# vinciDuino.net
KiCad netlist of a schematic drawn in EAGLE
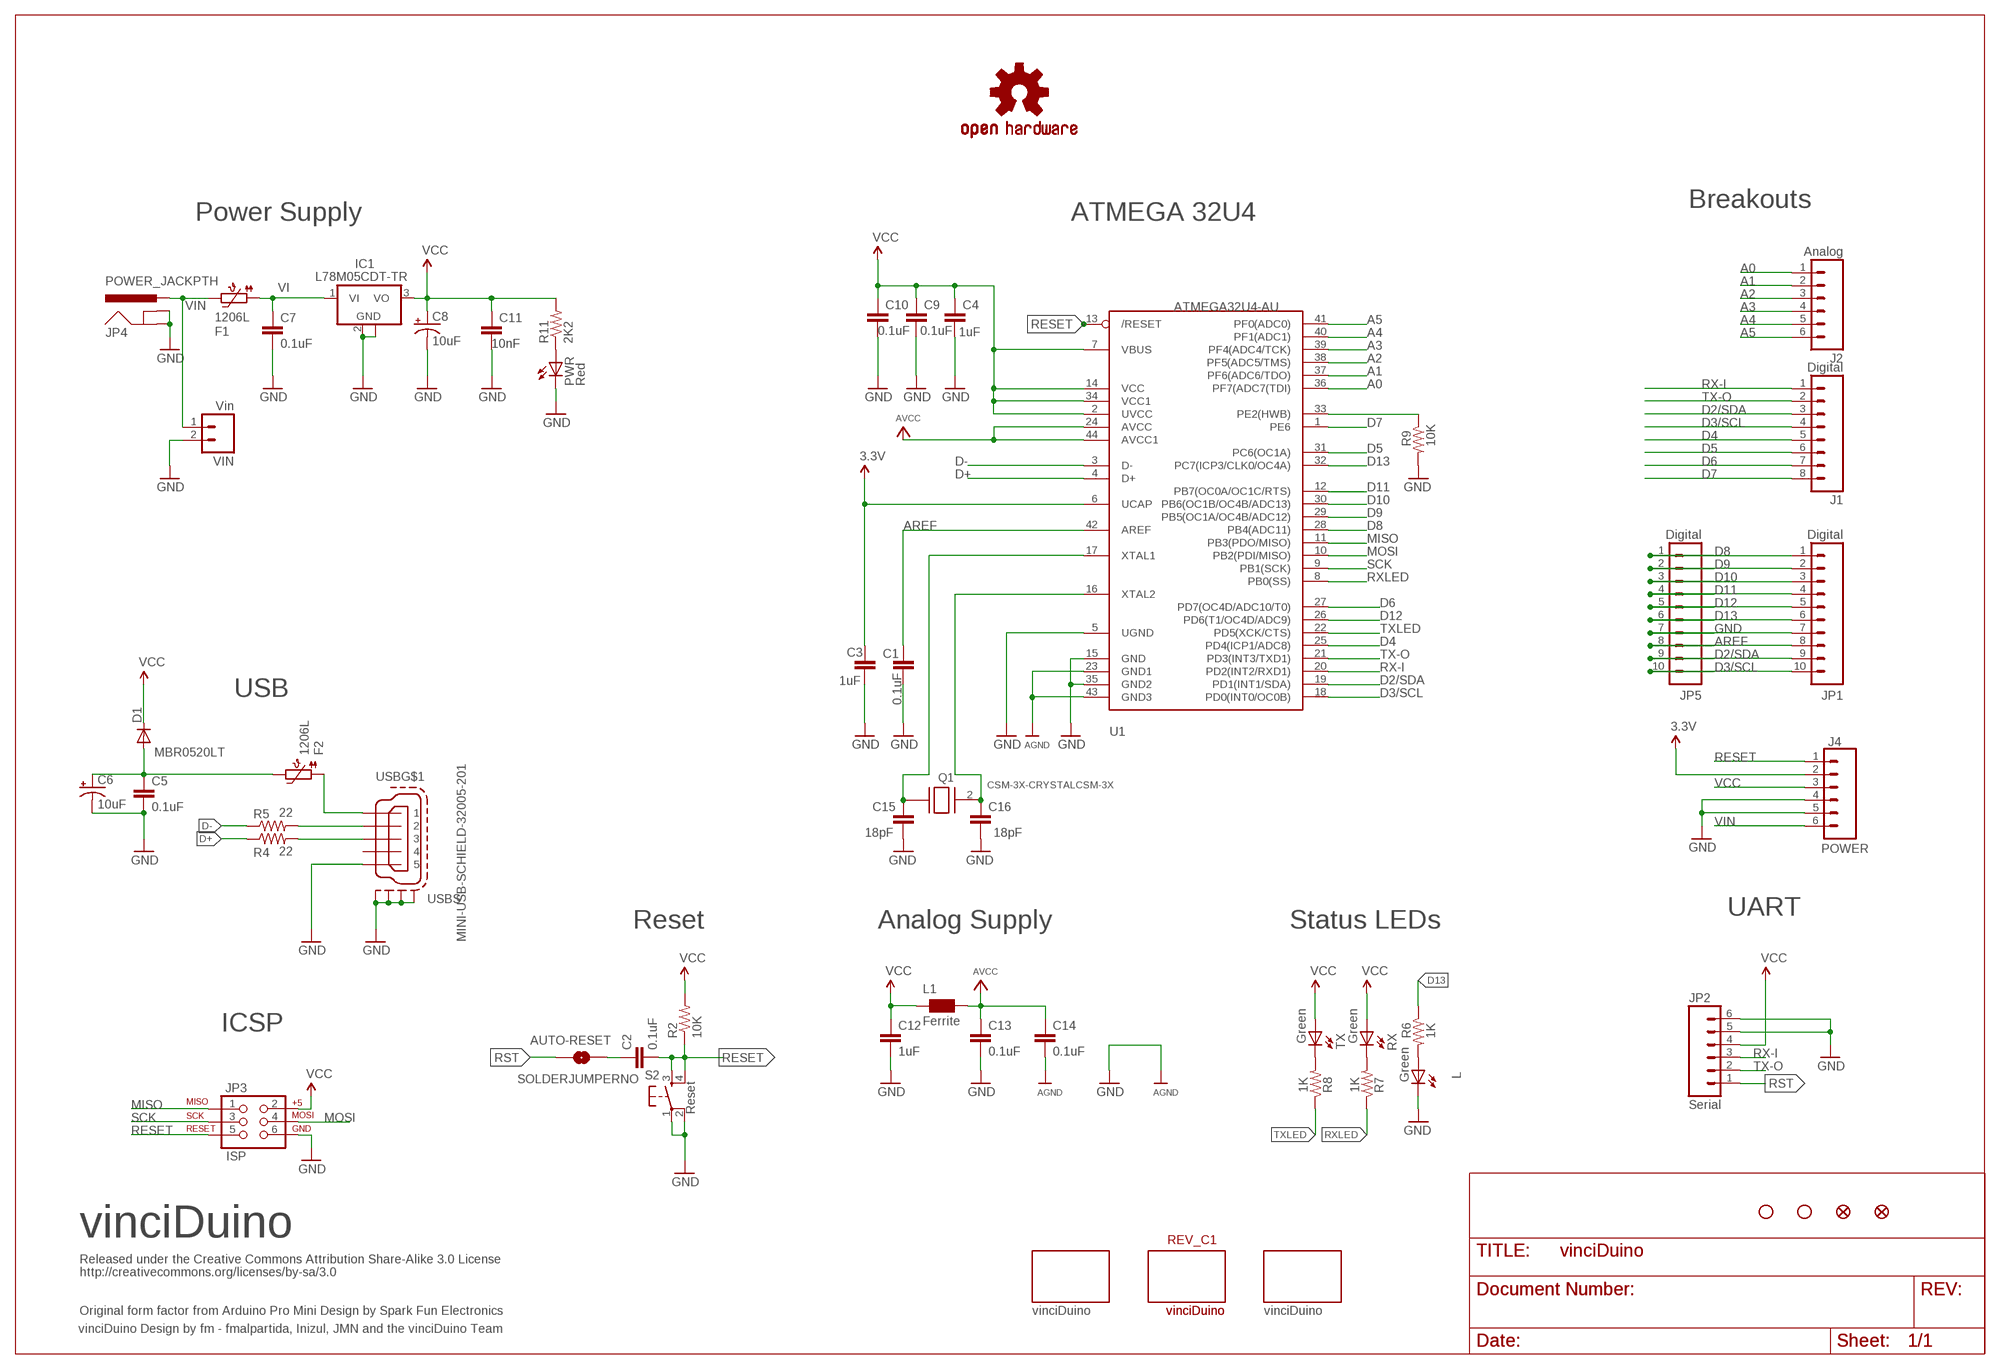
[diagram p0: schematic, sheet 1]

(export (version "E")
  (design (tool "Eeschema 10.0.6"))
  (components
    (comp (ref "AUTO-RESET")
      (value "SOLDERJUMPERNO")
      (footprint "eagle-import:SJ_2S-NO")
      (libsource (lib "eagle-import") (part "SOLDERJUMPERNO"))
    )
    (comp (ref "C1")
      (value "0.1uF")
      (footprint "eagle-import:1206")
      (libsource (lib "eagle-import") (part "CAP1206"))
    )
    (comp (ref "C2")
      (value "0.1uF")
      (footprint "eagle-import:1206")
      (libsource (lib "eagle-import") (part "CAP1206"))
    )
    (comp (ref "C3")
      (value "1uF")
      (footprint "eagle-import:1206")
      (libsource (lib "eagle-import") (part "CAP1206"))
    )
    (comp (ref "C4")
      (value "1uF")
      (footprint "eagle-import:1206")
      (libsource (lib "eagle-import") (part "CAP1206"))
    )
    (comp (ref "C5")
      (value "0.1uF")
      (footprint "eagle-import:1206")
      (libsource (lib "eagle-import") (part "CAP1206"))
    )
    (comp (ref "C6")
      (value "10uF")
      (footprint "eagle-import:EIA3216")
      (libsource (lib "eagle-import") (part "CAP_POL1206"))
    )
    (comp (ref "C7")
      (value "0.1uF")
      (footprint "eagle-import:1206")
      (libsource (lib "eagle-import") (part "CAP1206"))
    )
    (comp (ref "C8")
      (value "10uF")
      (footprint "eagle-import:EIA3216")
      (libsource (lib "eagle-import") (part "CAP_POL1206"))
    )
    (comp (ref "C9")
      (value "0.1uF")
      (footprint "eagle-import:1206")
      (libsource (lib "eagle-import") (part "CAP1206"))
    )
    (comp (ref "C10")
      (value "0.1uF")
      (footprint "eagle-import:1206")
      (libsource (lib "eagle-import") (part "CAP1206"))
    )
    (comp (ref "C11")
      (value "10nF")
      (footprint "eagle-import:1206")
      (libsource (lib "eagle-import") (part "CAP1206"))
    )
    (comp (ref "C12")
      (value "1uF")
      (footprint "eagle-import:1206")
      (libsource (lib "eagle-import") (part "CAP1206"))
    )
    (comp (ref "C13")
      (value "0.1uF")
      (footprint "eagle-import:1206")
      (libsource (lib "eagle-import") (part "CAP1206"))
    )
    (comp (ref "C14")
      (value "0.1uF")
      (footprint "eagle-import:1206")
      (libsource (lib "eagle-import") (part "CAP1206"))
    )
    (comp (ref "C15")
      (value "18pF")
      (footprint "eagle-import:1206")
      (libsource (lib "eagle-import") (part "CAP1206"))
    )
    (comp (ref "C16")
      (value "18pF")
      (footprint "eagle-import:1206")
      (libsource (lib "eagle-import") (part "CAP1206"))
    )
    (comp (ref "D1")
      (value "MBR0520LT")
      (footprint "eagle-import:SOD123")
      (libsource (lib "eagle-import") (part "MBR0520LT"))
    )
    (comp (ref "F1")
      (value "1206L")
      (footprint "eagle-import:1206_PTC")
      (libsource (lib "eagle-import") (part "PTC1206_L"))
    )
    (comp (ref "F2")
      (value "1206L")
      (footprint "eagle-import:1206_PTC")
      (libsource (lib "eagle-import") (part "PTC1206_L"))
    )
    (comp (ref "IC1")
      (value "L78M05CDT-TR")
      (footprint "eagle-import:SOT-223-DPAK")
      (libsource (lib "eagle-import") (part "78XX"))
    )
    (comp (ref "J1")
      (value "Digital")
      (footprint "eagle-import:1X08")
      (libsource (lib "eagle-import") (part "M081X08"))
    )
    (comp (ref "J2")
      (value "Analog")
      (footprint "eagle-import:1X06")
      (libsource (lib "eagle-import") (part "M06SIP"))
    )
    (comp (ref "J4")
      (value "POWER")
      (footprint "eagle-import:1X06")
      (libsource (lib "eagle-import") (part "M06SIP"))
    )
    (comp (ref "JP1")
      (value "Digital")
      (footprint "eagle-import:1X10")
      (libsource (lib "eagle-import") (part "M10{dblquote}"))
    )
    (comp (ref "JP2")
      (value "Serial")
      (footprint "eagle-import:1X06")
      (libsource (lib "eagle-import") (part "M06SIP"))
    )
    (comp (ref "JP3")
      (value "ISP")
      (footprint "eagle-import:2X3")
      (libsource (lib "eagle-import") (part "AVR_SPI_PRG_6PTH"))
    )
    (comp (ref "JP4")
      (value "POWER_JACKPTH")
      (footprint "eagle-import:POWER_JACK_PTH")
      (libsource (lib "eagle-import") (part "POWER_JACKPTH"))
    )
    (comp (ref "JP5")
      (value "Digital")
      (footprint "eagle-import:1X10")
      (libsource (lib "eagle-import") (part "M10{dblquote}"))
    )
    (comp (ref "L")
      (value "Green")
      (footprint "eagle-import:LED-1206")
      (libsource (lib "eagle-import") (part "LED1206"))
    )
    (comp (ref "L1")
      (value "Ferrite")
      (footprint "eagle-import:1206W")
      (libsource (lib "eagle-import") (part "WE-CBF_1206W"))
    )
    (comp (ref "PWR")
      (value "Red")
      (footprint "eagle-import:LED-1206")
      (libsource (lib "eagle-import") (part "LED1206"))
    )
    (comp (ref "Q1")
      (value "CSM-3X-CRYSTALCSM-3X")
      (footprint "eagle-import:CSM-3X")
      (libsource (lib "eagle-import") (part "CSM-3X-CRYSTALCSM-3X"))
    )
    (comp (ref "R2")
      (value "10K")
      (footprint "eagle-import:R1206")
      (libsource (lib "eagle-import") (part "R-US_R1206"))
    )
    (comp (ref "R4")
      (value "22")
      (footprint "eagle-import:R1206")
      (libsource (lib "eagle-import") (part "R-US_R1206"))
    )
    (comp (ref "R5")
      (value "22")
      (footprint "eagle-import:R1206")
      (libsource (lib "eagle-import") (part "R-US_R1206"))
    )
    (comp (ref "R6")
      (value "1K")
      (footprint "eagle-import:R1206")
      (libsource (lib "eagle-import") (part "R-US_R1206"))
    )
    (comp (ref "R7")
      (value "1K")
      (footprint "eagle-import:R1206")
      (libsource (lib "eagle-import") (part "R-US_R1206"))
    )
    (comp (ref "R8")
      (value "1K")
      (footprint "eagle-import:R1206")
      (libsource (lib "eagle-import") (part "R-US_R1206"))
    )
    (comp (ref "R9")
      (value "10K")
      (footprint "eagle-import:R1206")
      (libsource (lib "eagle-import") (part "R-US_R1206"))
    )
    (comp (ref "R11")
      (value "2K2")
      (footprint "eagle-import:R1206")
      (libsource (lib "eagle-import") (part "R-US_R1206"))
    )
    (comp (ref "REV_C1")
      (value "vinciDuino")
      (footprint "eagle-import:ARDUINO_FORUM")
      (libsource (lib "eagle-import") (part "BOARD_INFO_"))
    )
    (comp (ref "RX")
      (value "Green")
      (footprint "eagle-import:LED-1206")
      (libsource (lib "eagle-import") (part "LED1206"))
    )
    (comp (ref "S2")
      (value "Reset")
      (footprint "eagle-import:TACTILE_SWITCH_SMD")
      (libsource (lib "eagle-import") (part "TAC_SWITCHSMD"))
    )
    (comp (ref "TX")
      (value "Green")
      (footprint "eagle-import:LED-1206")
      (libsource (lib "eagle-import") (part "LED1206"))
    )
    (comp (ref "U$1")
      (value "VINCIDUINO_")
      (footprint "eagle-import:VINCIDUINO")
      (libsource (lib "eagle-import") (part "VINCIDUINO_25"))
    )
    (comp (ref "U$2")
      (value "FIDUCIAL1X2")
      (footprint "eagle-import:FIDUCIAL-1X2")
      (libsource (lib "eagle-import") (part "FIDUCIAL1X2"))
    )
    (comp (ref "U$3")
      (value "VINCIDUINO_15")
      (footprint "eagle-import:VINCIDUINO_VSMAL")
      (libsource (lib "eagle-import") (part "VINCIDUINO_15"))
    )
    (comp (ref "U$4")
      (value "FIDUCIAL1X2")
      (footprint "eagle-import:FIDUCIAL-1X2")
      (libsource (lib "eagle-import") (part "FIDUCIAL1X2"))
    )
    (comp (ref "U$9")
      (value "STAND-OFF")
      (footprint "eagle-import:STAND-OFF")
      (libsource (lib "eagle-import") (part "STAND-OFF"))
    )
    (comp (ref "U$10")
      (value "STAND-OFF")
      (footprint "eagle-import:STAND-OFF")
      (libsource (lib "eagle-import") (part "STAND-OFF"))
    )
    (comp (ref "U$14")
      (value "OSHW-LOGOS")
      (footprint "eagle-import:OSHW-LOGO-S")
      (libsource (lib "eagle-import") (part "OSHW-LOGOS"))
    )
    (comp (ref "U1")
      (value "ATMEGA32U4-AU")
      (footprint "eagle-import:TQFP44")
      (libsource (lib "eagle-import") (part "ATMEGA32U4-AU"))
    )
    (comp (ref "USB")
      (value "MINI-USB-SCHIELD-32005-201")
      (footprint "eagle-import:32005-201")
      (libsource (lib "eagle-import") (part "MINI-USB-SCHIELD-32005-201"))
    )
    (comp (ref "VIN")
      (value "Vin")
      (footprint "eagle-import:1X02_NO_SILK")
      (libsource (lib "eagle-import") (part "M021X02_NO_SILK"))
    )
  )
  (nets
    (net (code "1") (name "/A0") (class "Default")
      (node (ref "J2") (pin "1") (pinfunction "1_1") (pintype "passive"))
      (node (ref "U1") (pin "36") (pinfunction "PF7(ADC7(TDI)_36") (pintype "bidirectional"))
    )
    (net (code "2") (name "/A1") (class "Default")
      (node (ref "J2") (pin "2") (pinfunction "2_2") (pintype "passive"))
      (node (ref "U1") (pin "37") (pinfunction "PF6(ADC6/TDO)_37") (pintype "bidirectional"))
    )
    (net (code "3") (name "/A2") (class "Default")
      (node (ref "J2") (pin "3") (pinfunction "3_3") (pintype "passive"))
      (node (ref "U1") (pin "38") (pinfunction "PF5(ADC5/TMS)_38") (pintype "bidirectional"))
    )
    (net (code "4") (name "/A3") (class "Default")
      (node (ref "J2") (pin "4") (pinfunction "4_4") (pintype "passive"))
      (node (ref "U1") (pin "39") (pinfunction "PF4(ADC4/TCK)_39") (pintype "bidirectional"))
    )
    (net (code "5") (name "/A4") (class "Default")
      (node (ref "J2") (pin "5") (pinfunction "5_5") (pintype "passive"))
      (node (ref "U1") (pin "40") (pinfunction "PF1(ADC1)_40") (pintype "bidirectional"))
    )
    (net (code "6") (name "/A5") (class "Default")
      (node (ref "J2") (pin "6") (pinfunction "6_6") (pintype "passive"))
      (node (ref "U1") (pin "41") (pinfunction "PF0(ADC0)_41") (pintype "bidirectional"))
    )
    (net (code "7") (name "/AREF") (class "Default")
      (node (ref "C1") (pin "2") (pinfunction "2_2") (pintype "passive"))
      (node (ref "JP1") (pin "8") (pinfunction "8_8") (pintype "passive"))
      (node (ref "JP5") (pin "8") (pinfunction "8_8") (pintype "passive"))
      (node (ref "U1") (pin "42") (pinfunction "AREF_42") (pintype "bidirectional"))
    )
    (net (code "8") (name "/D2{slash}SDA") (class "Default")
      (node (ref "J1") (pin "3") (pinfunction "3_3") (pintype "passive"))
      (node (ref "JP1") (pin "9") (pinfunction "9_9") (pintype "passive"))
      (node (ref "JP5") (pin "9") (pinfunction "9_9") (pintype "passive"))
      (node (ref "U1") (pin "19") (pinfunction "PD1(INT1/SDA)_19") (pintype "bidirectional"))
    )
    (net (code "9") (name "/D3{slash}SCL") (class "Default")
      (node (ref "J1") (pin "4") (pinfunction "4_4") (pintype "passive"))
      (node (ref "JP1") (pin "10") (pinfunction "10_10") (pintype "passive"))
      (node (ref "JP5") (pin "10") (pinfunction "10_10") (pintype "passive"))
      (node (ref "U1") (pin "18") (pinfunction "PD0(INT0/OC0B)_18") (pintype "bidirectional"))
    )
    (net (code "10") (name "/D4") (class "Default")
      (node (ref "J1") (pin "5") (pinfunction "5_5") (pintype "passive"))
      (node (ref "U1") (pin "25") (pinfunction "PD4(ICP1/ADC8)_25") (pintype "bidirectional"))
    )
    (net (code "11") (name "/D5") (class "Default")
      (node (ref "J1") (pin "6") (pinfunction "6_6") (pintype "passive"))
      (node (ref "U1") (pin "31") (pinfunction "PC6(OC1A)_31") (pintype "bidirectional"))
    )
    (net (code "12") (name "/D6") (class "Default")
      (node (ref "J1") (pin "7") (pinfunction "7_7") (pintype "passive"))
      (node (ref "U1") (pin "27") (pinfunction "PD7(OC4D/ADC10/T0)_27") (pintype "bidirectional"))
    )
    (net (code "13") (name "/D7") (class "Default")
      (node (ref "J1") (pin "8") (pinfunction "8_8") (pintype "passive"))
      (node (ref "U1") (pin "1") (pinfunction "PE6_1") (pintype "bidirectional"))
    )
    (net (code "14") (name "/D8") (class "Default")
      (node (ref "JP1") (pin "1") (pinfunction "1_1") (pintype "passive"))
      (node (ref "JP5") (pin "1") (pinfunction "1_1") (pintype "passive"))
      (node (ref "U1") (pin "28") (pinfunction "PB4(ADC11)_28") (pintype "bidirectional"))
    )
    (net (code "15") (name "/D9") (class "Default")
      (node (ref "JP1") (pin "2") (pinfunction "2_2") (pintype "passive"))
      (node (ref "JP5") (pin "2") (pinfunction "2_2") (pintype "passive"))
      (node (ref "U1") (pin "29") (pinfunction "PB5(OC1A/OC4B/ADC12)_29") (pintype "bidirectional"))
    )
    (net (code "16") (name "/D10") (class "Default")
      (node (ref "JP1") (pin "3") (pinfunction "3_3") (pintype "passive"))
      (node (ref "JP5") (pin "3") (pinfunction "3_3") (pintype "passive"))
      (node (ref "U1") (pin "30") (pinfunction "PB6(OC1B/OC4B/ADC13)_30") (pintype "bidirectional"))
    )
    (net (code "17") (name "/D11") (class "Default")
      (node (ref "JP1") (pin "4") (pinfunction "4_4") (pintype "passive"))
      (node (ref "JP5") (pin "4") (pinfunction "4_4") (pintype "passive"))
      (node (ref "U1") (pin "12") (pinfunction "PB7(OC0A/OC1C/RTS)_12") (pintype "bidirectional"))
    )
    (net (code "18") (name "/D12") (class "Default")
      (node (ref "JP1") (pin "5") (pinfunction "5_5") (pintype "passive"))
      (node (ref "JP5") (pin "5") (pinfunction "5_5") (pintype "passive"))
      (node (ref "U1") (pin "26") (pinfunction "PD6(T1/OC4D/ADC9)_26") (pintype "bidirectional"))
    )
    (net (code "19") (name "/MISO") (class "Default")
      (node (ref "JP3") (pin "1") (pinfunction "1_1") (pintype "passive"))
      (node (ref "U1") (pin "11") (pinfunction "PB3(PDO/MISO)_11") (pintype "bidirectional"))
    )
    (net (code "20") (name "/MOSI") (class "Default")
      (node (ref "JP3") (pin "4") (pinfunction "4_4") (pintype "passive"))
      (node (ref "U1") (pin "10") (pinfunction "PB2(PDI/MISO)_10") (pintype "bidirectional"))
    )
    (net (code "21") (name "/RX-I") (class "Default")
      (node (ref "J1") (pin "1") (pinfunction "1_1") (pintype "passive"))
      (node (ref "JP2") (pin "3") (pinfunction "3_3") (pintype "passive"))
      (node (ref "U1") (pin "20") (pinfunction "PD2(INT2/RXD1)_20") (pintype "bidirectional"))
    )
    (net (code "22") (name "/SCK") (class "Default")
      (node (ref "JP3") (pin "3") (pinfunction "3_3") (pintype "passive"))
      (node (ref "U1") (pin "9") (pinfunction "PB1(SCK)_9") (pintype "bidirectional"))
    )
    (net (code "23") (name "/TX-O") (class "Default")
      (node (ref "J1") (pin "2") (pinfunction "2_2") (pintype "passive"))
      (node (ref "JP2") (pin "2") (pinfunction "2_2") (pintype "passive"))
      (node (ref "U1") (pin "21") (pinfunction "PD3(INT3/TXD1)_21") (pintype "bidirectional"))
    )
    (net (code "24") (name "/VI") (class "Default")
      (node (ref "C7") (pin "1") (pinfunction "1_1") (pintype "passive"))
      (node (ref "F1") (pin "1") (pinfunction "1_1") (pintype "passive"))
      (node (ref "IC1") (pin "1") (pinfunction "VI_1") (pintype "input"))
    )
    (net (code "25") (name "/VIN") (class "Default")
      (node (ref "F1") (pin "2") (pinfunction "2_2") (pintype "passive"))
      (node (ref "J4") (pin "6") (pinfunction "6_6") (pintype "passive"))
      (node (ref "JP4") (pin "PWR") (pinfunction "PWR_PWR") (pintype "bidirectional"))
      (node (ref "VIN") (pin "1") (pinfunction "1_1") (pintype "passive"))
    )
    (net (code "26") (name "3.3V") (class "Default")
      (node (ref "C3") (pin "1") (pinfunction "1_1") (pintype "passive"))
      (node (ref "J4") (pin "2") (pinfunction "2_2") (pintype "passive"))
      (node (ref "U1") (pin "6") (pinfunction "UCAP_6") (pintype "bidirectional"))
    )
    (net (code "27") (name "AGND") (class "Default")
      (node (ref "C1") (pin "1") (pinfunction "1_1") (pintype "passive"))
      (node (ref "C10") (pin "2") (pinfunction "2_2") (pintype "passive"))
      (node (ref "C11") (pin "2") (pinfunction "2_2") (pintype "passive"))
      (node (ref "C12") (pin "2") (pinfunction "2_2") (pintype "passive"))
      (node (ref "C13") (pin "2") (pinfunction "2_2") (pintype "passive"))
      (node (ref "C14") (pin "2") (pinfunction "2_2") (pintype "passive"))
      (node (ref "C15") (pin "2") (pinfunction "2_2") (pintype "passive"))
      (node (ref "C16") (pin "2") (pinfunction "2_2") (pintype "passive"))
      (node (ref "C3") (pin "2") (pinfunction "2_2") (pintype "passive"))
      (node (ref "C4") (pin "2") (pinfunction "2_2") (pintype "passive"))
      (node (ref "C5") (pin "2") (pinfunction "2_2") (pintype "passive"))
      (node (ref "C6") (pin "C") (pinfunction "-_C") (pintype "passive"))
      (node (ref "C7") (pin "2") (pinfunction "2_2") (pintype "passive"))
      (node (ref "C8") (pin "C") (pinfunction "-_C") (pintype "passive"))
      (node (ref "C9") (pin "2") (pinfunction "2_2") (pintype "passive"))
      (node (ref "IC1") (pin "2") (pinfunction "GND_2") (pintype "passive"))
      (node (ref "IC1") (pin "4") (pinfunction "GND_4") (pintype "passive"))
      (node (ref "J4") (pin "4") (pinfunction "4_4") (pintype "passive"))
      (node (ref "J4") (pin "5") (pinfunction "5_5") (pintype "passive"))
      (node (ref "JP1") (pin "7") (pinfunction "7_7") (pintype "passive"))
      (node (ref "JP2") (pin "5") (pinfunction "5_5") (pintype "passive"))
      (node (ref "JP2") (pin "6") (pinfunction "6_6") (pintype "passive"))
      (node (ref "JP3") (pin "6") (pinfunction "6_6") (pintype "passive"))
      (node (ref "JP4") (pin "GND") (pinfunction "GND_GND") (pintype "bidirectional"))
      (node (ref "JP4") (pin "GNDBREAK") (pinfunction "GNDBREAK_GNDBREAK") (pintype "bidirectional"))
      (node (ref "JP5") (pin "7") (pinfunction "7_7") (pintype "passive"))
      (node (ref "L") (pin "C") (pinfunction "C_C") (pintype "passive"))
      (node (ref "PWR") (pin "C") (pinfunction "C_C") (pintype "passive"))
      (node (ref "R9") (pin "2") (pinfunction "2_2") (pintype "passive"))
      (node (ref "S2") (pin "1") (pinfunction "1_1") (pintype "passive"))
      (node (ref "S2") (pin "2") (pinfunction "2_2") (pintype "passive"))
      (node (ref "U1") (pin "15") (pinfunction "GND_15") (pintype "bidirectional"))
      (node (ref "U1") (pin "23") (pinfunction "GND1_23") (pintype "bidirectional"))
      (node (ref "U1") (pin "35") (pinfunction "GND2_35") (pintype "bidirectional"))
      (node (ref "U1") (pin "43") (pinfunction "GND3_43") (pintype "bidirectional"))
      (node (ref "U1") (pin "5") (pinfunction "UGND_5") (pintype "bidirectional"))
      (node (ref "USB") (pin "5") (pinfunction "5_5") (pintype "passive"))
      (node (ref "USB") (pin "M1") (pinfunction "S1_M1") (pintype "passive"))
      (node (ref "USB") (pin "M2") (pinfunction "S2_M2") (pintype "passive"))
      (node (ref "USB") (pin "M3") (pinfunction "S3_M3") (pintype "passive"))
      (node (ref "USB") (pin "M4") (pinfunction "S4_M4") (pintype "passive"))
      (node (ref "VIN") (pin "2") (pinfunction "2_2") (pintype "passive"))
    )
    (net (code "28") (name "AVCC") (class "Default")
      (node (ref "C13") (pin "1") (pinfunction "1_1") (pintype "passive"))
      (node (ref "C14") (pin "1") (pinfunction "1_1") (pintype "passive"))
      (node (ref "L1") (pin "2") (pinfunction "2_2") (pintype "passive"))
      (node (ref "U1") (pin "24") (pinfunction "AVCC_24") (pintype "bidirectional"))
      (node (ref "U1") (pin "44") (pinfunction "AVCC1_44") (pintype "bidirectional"))
    )
    (net (code "29") (name "D+") (class "Default")
      (node (ref "R4") (pin "1") (pinfunction "1_1") (pintype "passive"))
      (node (ref "U1") (pin "4") (pinfunction "D+_4") (pintype "bidirectional"))
    )
    (net (code "30") (name "D-") (class "Default")
      (node (ref "R5") (pin "1") (pinfunction "1_1") (pintype "passive"))
      (node (ref "U1") (pin "3") (pinfunction "D-_3") (pintype "bidirectional"))
    )
    (net (code "31") (name "D13") (class "Default")
      (node (ref "JP1") (pin "6") (pinfunction "6_6") (pintype "passive"))
      (node (ref "JP5") (pin "6") (pinfunction "6_6") (pintype "passive"))
      (node (ref "R6") (pin "1") (pinfunction "1_1") (pintype "passive"))
      (node (ref "U1") (pin "32") (pinfunction "PC7(ICP3/CLK0/OC4A)_32") (pintype "bidirectional"))
    )
    (net (code "32") (name "Net-(AUTO-RESET-Pad2)") (class "Default")
      (node (ref "AUTO-RESET") (pin "2") (pinfunction "2_2") (pintype "passive"))
      (node (ref "C2") (pin "1") (pinfunction "1_1") (pintype "passive"))
    )
    (net (code "33") (name "Net-(C6-+)") (class "Default")
      (node (ref "C5") (pin "1") (pinfunction "1_1") (pintype "passive"))
      (node (ref "C6") (pin "A") (pinfunction "+_A") (pintype "passive"))
      (node (ref "D1") (pin "A") (pinfunction "A_A") (pintype "passive"))
      (node (ref "F2") (pin "2") (pinfunction "2_2") (pintype "passive"))
    )
    (net (code "34") (name "Net-(F2-Pad1)") (class "Default")
      (node (ref "F2") (pin "1") (pinfunction "1_1") (pintype "passive"))
      (node (ref "USB") (pin "1") (pinfunction "1_1") (pintype "passive"))
    )
    (net (code "35") (name "Net-(L-PadA)") (class "Default")
      (node (ref "L") (pin "A") (pinfunction "A_A") (pintype "passive"))
      (node (ref "R6") (pin "2") (pinfunction "2_2") (pintype "passive"))
    )
    (net (code "36") (name "Net-(PWR-PadA)") (class "Default")
      (node (ref "PWR") (pin "A") (pinfunction "A_A") (pintype "passive"))
      (node (ref "R11") (pin "1") (pinfunction "1_1") (pintype "passive"))
    )
    (net (code "37") (name "Net-(R4-Pad2)") (class "Default")
      (node (ref "R4") (pin "2") (pinfunction "2_2") (pintype "passive"))
      (node (ref "USB") (pin "3") (pinfunction "3_3") (pintype "passive"))
    )
    (net (code "38") (name "Net-(R5-Pad2)") (class "Default")
      (node (ref "R5") (pin "2") (pinfunction "2_2") (pintype "passive"))
      (node (ref "USB") (pin "2") (pinfunction "2_2") (pintype "passive"))
    )
    (net (code "39") (name "Net-(R7-Pad2)") (class "Default")
      (node (ref "R7") (pin "2") (pinfunction "2_2") (pintype "passive"))
      (node (ref "RX") (pin "C") (pinfunction "C_C") (pintype "passive"))
    )
    (net (code "40") (name "Net-(R8-Pad2)") (class "Default")
      (node (ref "R8") (pin "2") (pinfunction "2_2") (pintype "passive"))
      (node (ref "TX") (pin "C") (pinfunction "C_C") (pintype "passive"))
    )
    (net (code "41") (name "Net-(U1-PE2(HWB))") (class "Default")
      (node (ref "R9") (pin "1") (pinfunction "1_1") (pintype "passive"))
      (node (ref "U1") (pin "33") (pinfunction "PE2(HWB)_33") (pintype "bidirectional"))
    )
    (net (code "42") (name "Net-(U1-XTAL1)") (class "Default")
      (node (ref "C15") (pin "1") (pinfunction "1_1") (pintype "passive"))
      (node (ref "Q1") (pin "1") (pinfunction "1_1") (pintype "bidirectional"))
      (node (ref "U1") (pin "17") (pinfunction "XTAL1_17") (pintype "bidirectional"))
    )
    (net (code "43") (name "Net-(U1-XTAL2)") (class "Default")
      (node (ref "C16") (pin "1") (pinfunction "1_1") (pintype "passive"))
      (node (ref "Q1") (pin "2") (pinfunction "2_2") (pintype "bidirectional"))
      (node (ref "U1") (pin "16") (pinfunction "XTAL2_16") (pintype "bidirectional"))
    )
    (net (code "44") (name "RESET") (class "Default")
      (node (ref "C2") (pin "2") (pinfunction "2_2") (pintype "passive"))
      (node (ref "J4") (pin "1") (pinfunction "1_1") (pintype "passive"))
      (node (ref "JP3") (pin "5") (pinfunction "5_5") (pintype "passive"))
      (node (ref "R2") (pin "1") (pinfunction "1_1") (pintype "passive"))
      (node (ref "S2") (pin "3") (pinfunction "3_3") (pintype "passive"))
      (node (ref "S2") (pin "4") (pinfunction "4_4") (pintype "passive"))
      (node (ref "U1") (pin "13") (pinfunction "/RESET_13") (pintype "bidirectional"))
    )
    (net (code "45") (name "RST") (class "Default")
      (node (ref "AUTO-RESET") (pin "1") (pinfunction "1_1") (pintype "passive"))
      (node (ref "JP2") (pin "1") (pinfunction "1_1") (pintype "passive"))
    )
    (net (code "46") (name "RXLED") (class "Default")
      (node (ref "R7") (pin "1") (pinfunction "1_1") (pintype "passive"))
      (node (ref "U1") (pin "8") (pinfunction "PB0(SS)_8") (pintype "bidirectional"))
    )
    (net (code "47") (name "TXLED") (class "Default")
      (node (ref "R8") (pin "1") (pinfunction "1_1") (pintype "passive"))
      (node (ref "U1") (pin "22") (pinfunction "PD5(XCK/CTS)_22") (pintype "bidirectional"))
    )
    (net (code "48") (name "VCC") (class "Default")
      (node (ref "C10") (pin "1") (pinfunction "1_1") (pintype "passive"))
      (node (ref "C11") (pin "1") (pinfunction "1_1") (pintype "passive"))
      (node (ref "C12") (pin "1") (pinfunction "1_1") (pintype "passive"))
      (node (ref "C4") (pin "1") (pinfunction "1_1") (pintype "passive"))
      (node (ref "C8") (pin "A") (pinfunction "+_A") (pintype "passive"))
      (node (ref "C9") (pin "1") (pinfunction "1_1") (pintype "passive"))
      (node (ref "D1") (pin "C") (pinfunction "C_C") (pintype "passive"))
      (node (ref "IC1") (pin "3") (pinfunction "VO_3") (pintype "passive"))
      (node (ref "J4") (pin "3") (pinfunction "3_3") (pintype "passive"))
      (node (ref "JP2") (pin "4") (pinfunction "4_4") (pintype "passive"))
      (node (ref "JP3") (pin "2") (pinfunction "2_2") (pintype "passive"))
      (node (ref "L1") (pin "1") (pinfunction "1_1") (pintype "passive"))
      (node (ref "R11") (pin "2") (pinfunction "2_2") (pintype "passive"))
      (node (ref "R2") (pin "2") (pinfunction "2_2") (pintype "passive"))
      (node (ref "RX") (pin "A") (pinfunction "A_A") (pintype "passive"))
      (node (ref "TX") (pin "A") (pinfunction "A_A") (pintype "passive"))
      (node (ref "U1") (pin "14") (pinfunction "VCC_14") (pintype "bidirectional"))
      (node (ref "U1") (pin "2") (pinfunction "UVCC_2") (pintype "bidirectional"))
      (node (ref "U1") (pin "34") (pinfunction "VCC1_34") (pintype "bidirectional"))
      (node (ref "U1") (pin "7") (pinfunction "VBUS_7") (pintype "bidirectional"))
    )
    (net (code "49") (name "unconnected-(USB-Pad4)") (class "Default")
      (node (ref "USB") (pin "4") (pinfunction "4_4") (pintype "passive"))
    )
  )
)
